# Redhat-Thumbprint.net
KiCad netlist of a schematic drawn in EAGLE
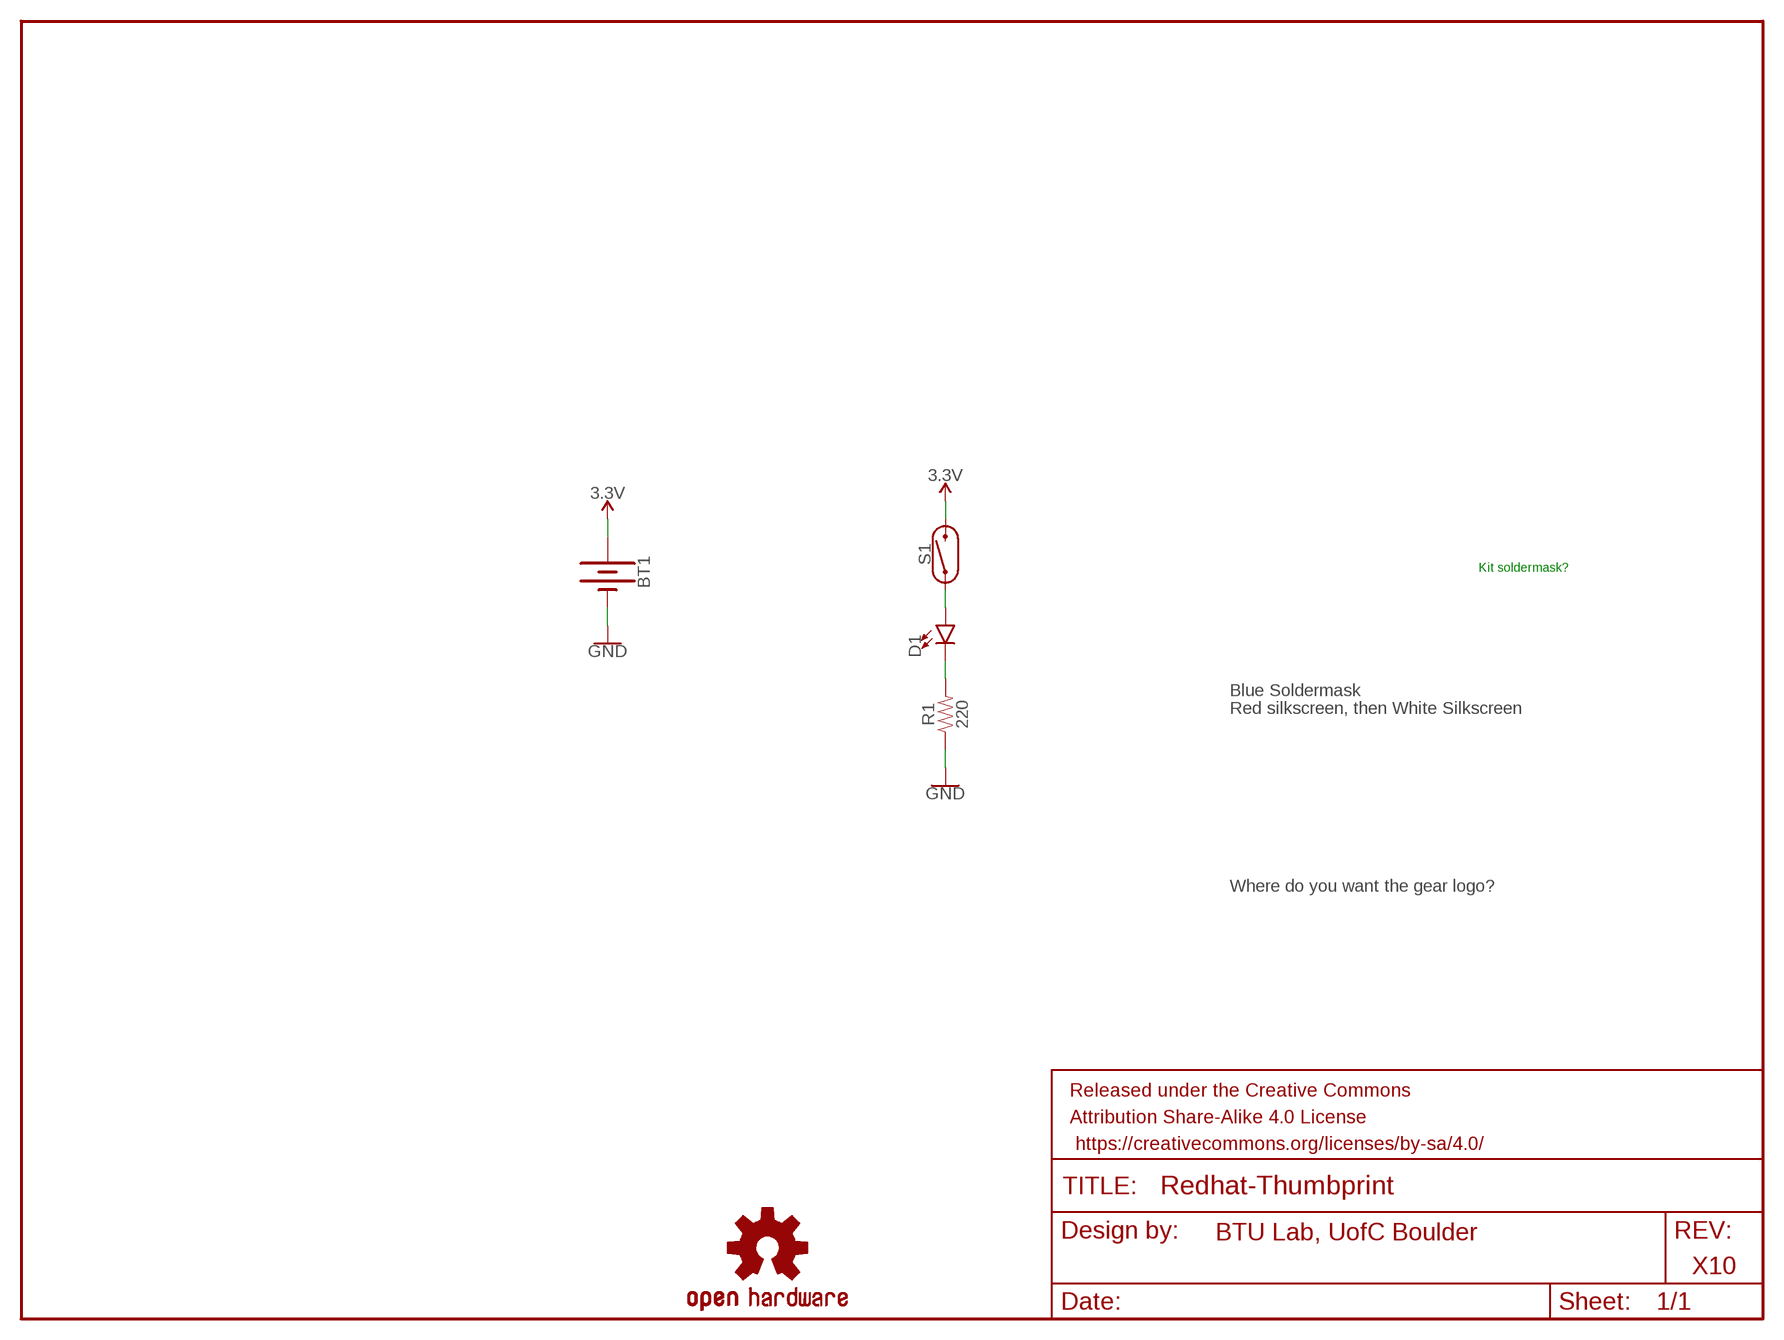
[diagram p0: schematic, sheet 1]

(export (version "E")
  (design (tool "Eeschema 10.0.6"))
  (components
    (comp (ref "BT1")
      (value "BATTERY-20MM_PTH")
      (footprint "eagle-import:BATTCOM_20MM_PTH")
      (libsource (lib "eagle-import") (part "BATTERY-20MM_PTH"))
    )
    (comp (ref "D1")
      (value "LEDRED")
      (footprint "eagle-import:LED_5MM_EXTRASILK")
      (libsource (lib "eagle-import") (part "LEDRED"))
    )
    (comp (ref "FRAME1")
      (value "FRAME-LETTER")
      (footprint "eagle-import:CREATIVE_COMMONS")
      (libsource (lib "eagle-import") (part "FRAME-LETTER"))
    )
    (comp (ref "LOGO4")
      (value "OSHW-LOGOS")
      (footprint "eagle-import:OSHW-LOGO-S")
      (libsource (lib "eagle-import") (part "OSHW-LOGOS"))
    )
    (comp (ref "R1")
      (value "220")
      (footprint "eagle-import:AXIAL-0.3")
      (libsource (lib "eagle-import") (part "1KOHM-HORIZ-1/4W-1%"))
    )
    (comp (ref "S1")
      (value "REED_SWITCH-PTH-INSULATED")
      (footprint "eagle-import:REED_SWITCH_PLASTIC")
      (libsource (lib "eagle-import") (part "REED_SWITCH-PTH-INSULATED"))
    )
  )
  (nets
    (net (code "1") (name "3.3V") (class "Default")
      (node (ref "BT1") (pin "1") (pinfunction "+_1") (pintype "power_in"))
      (node (ref "S1") (pin "P$2") (pinfunction "2_P$2") (pintype "passive"))
    )
    (net (code "2") (name "GND") (class "Default")
      (node (ref "BT1") (pin "2") (pinfunction "-_2") (pintype "power_in"))
      (node (ref "R1") (pin "P$1") (pinfunction "1_P$1") (pintype "passive"))
    )
    (net (code "3") (name "Net-(D1-C)") (class "Default")
      (node (ref "D1") (pin "K") (pinfunction "C_K") (pintype "passive"))
      (node (ref "R1") (pin "P$2") (pinfunction "2_P$2") (pintype "passive"))
    )
    (net (code "4") (name "Net-(S1-1)") (class "Default")
      (node (ref "D1") (pin "A") (pinfunction "A_A") (pintype "passive"))
      (node (ref "S1") (pin "P$1") (pinfunction "1_P$1") (pintype "passive"))
    )
  )
)
